# MCP23017.net
KiCad netlist of a schematic drawn in Altium Designer
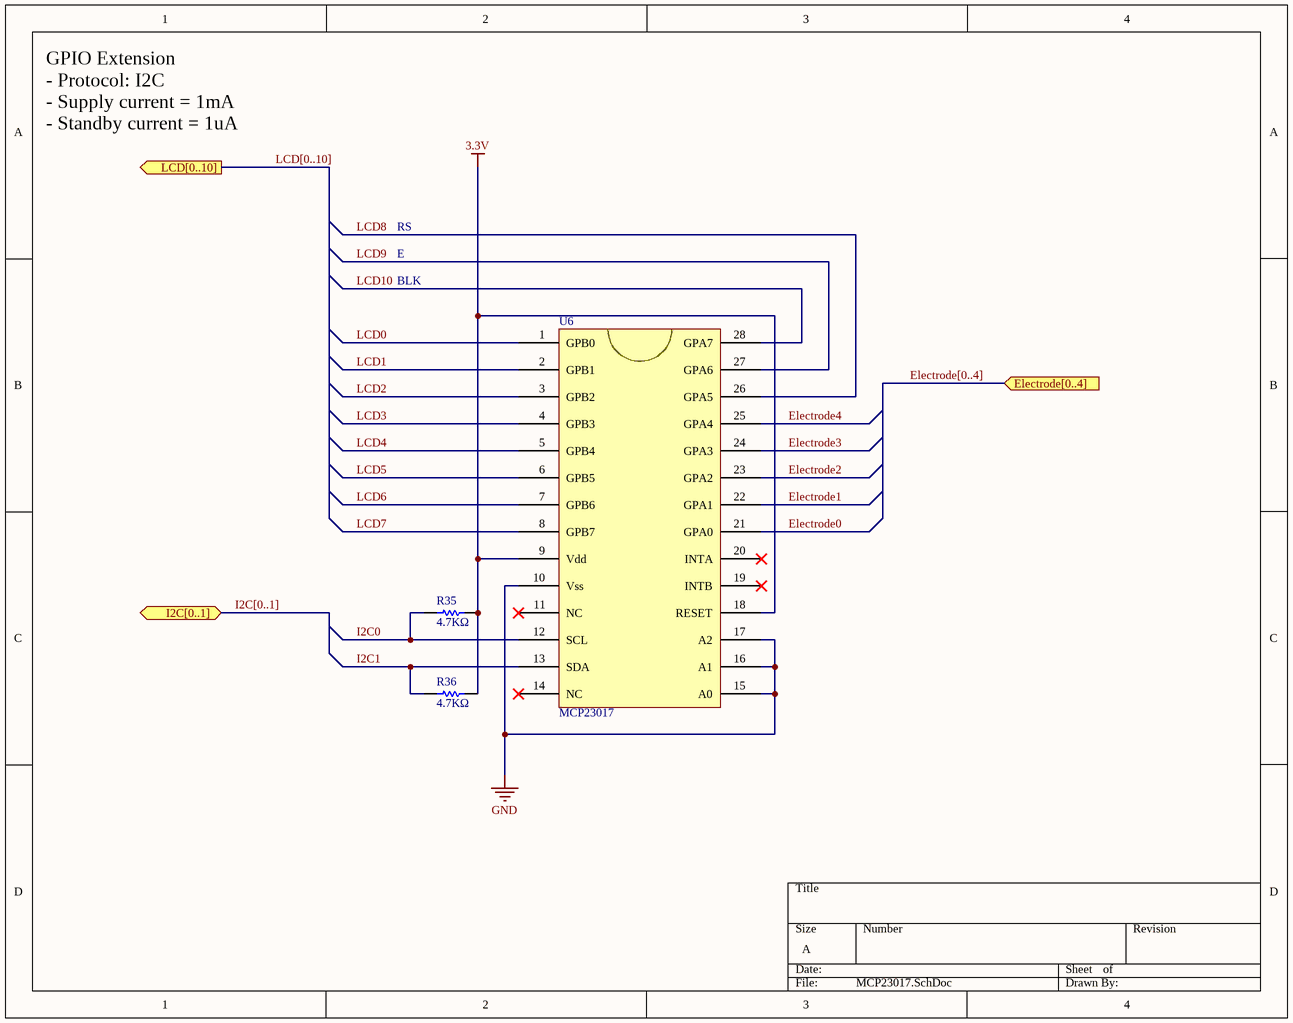
[diagram p0: MCP23017.SchDoc]

(export (version "E")
  (design (tool "Eeschema 10.0.6"))
  (components
    (comp (ref "R35")
      (value "4.7KΩ")
      (footprint "R0603")
      (description "Resistor")
      (fields (field (name "MANUFACTURER") "MULTICOMP") (field (name "PUBLISHER") "Altium Limited"))
      (libsource (lib "Miscellaneous Devices") (part "Res1"))
    )
    (comp (ref "R36")
      (value "4.7KΩ")
      (footprint "R0603")
      (description "Resistor")
      (fields (field (name "MANUFACTURER") "MULTICOMP") (field (name "PUBLISHER") "Altium Limited"))
      (libsource (lib "Miscellaneous Devices") (part "Res1"))
    )
    (comp (ref "U6")
      (value "MCP23017")
      (footprint "MCP23017")
      (description "GPIOExpander")
      (fields (field (name "MANUFACTURER") "MICROCHIP"))
      (libsource (lib "Electroplant") (part "MPC23017"))
    )
  )
  (nets
    (net (code "1") (name "/Electrode0") (class "Default")
      (node (ref "U6") (pin "21") (pinfunction "GPA0_21") (pintype "passive"))
    )
    (net (code "2") (name "/Electrode1") (class "Default")
      (node (ref "U6") (pin "22") (pinfunction "GPA1_22") (pintype "passive"))
    )
    (net (code "3") (name "/Electrode2") (class "Default")
      (node (ref "U6") (pin "23") (pinfunction "GPA2_23") (pintype "passive"))
    )
    (net (code "4") (name "/Electrode3") (class "Default")
      (node (ref "U6") (pin "24") (pinfunction "GPA3_24") (pintype "passive"))
    )
    (net (code "5") (name "/Electrode4") (class "Default")
      (node (ref "U6") (pin "25") (pinfunction "GPA4_25") (pintype "passive"))
    )
    (net (code "7") (name "/I2C0") (class "Default")
      (node (ref "R35") (pin "1") (pinfunction "1_1") (pintype "passive"))
      (node (ref "U6") (pin "12") (pinfunction "SCL_12") (pintype "passive"))
    )
    (net (code "8") (name "/I2C1") (class "Default")
      (node (ref "R36") (pin "1") (pinfunction "1_1") (pintype "passive"))
      (node (ref "U6") (pin "13") (pinfunction "SDA_13") (pintype "passive"))
    )
    (net (code "10") (name "/LCD0") (class "Default")
      (node (ref "U6") (pin "1") (pinfunction "GPB0_1") (pintype "passive"))
    )
    (net (code "11") (name "/LCD1") (class "Default")
      (node (ref "U6") (pin "2") (pinfunction "GPB1_2") (pintype "passive"))
    )
    (net (code "12") (name "/LCD2") (class "Default")
      (node (ref "U6") (pin "3") (pinfunction "GPB2_3") (pintype "passive"))
    )
    (net (code "13") (name "/LCD3") (class "Default")
      (node (ref "U6") (pin "4") (pinfunction "GPB3_4") (pintype "passive"))
    )
    (net (code "14") (name "/LCD4") (class "Default")
      (node (ref "U6") (pin "5") (pinfunction "GPB4_5") (pintype "passive"))
    )
    (net (code "15") (name "/LCD5") (class "Default")
      (node (ref "U6") (pin "6") (pinfunction "GPB5_6") (pintype "passive"))
    )
    (net (code "16") (name "/LCD6") (class "Default")
      (node (ref "U6") (pin "7") (pinfunction "GPB6_7") (pintype "passive"))
    )
    (net (code "17") (name "/LCD7") (class "Default")
      (node (ref "U6") (pin "8") (pinfunction "GPB7_8") (pintype "passive"))
    )
    (net (code "18") (name "/LCD8") (class "Default")
      (node (ref "U6") (pin "26") (pinfunction "GPA5_26") (pintype "passive"))
    )
    (net (code "19") (name "/LCD9") (class "Default")
      (node (ref "U6") (pin "27") (pinfunction "GPA6_27") (pintype "passive"))
    )
    (net (code "20") (name "/LCD10") (class "Default")
      (node (ref "U6") (pin "28") (pinfunction "GPA7_28") (pintype "passive"))
    )
    (net (code "22") (name "3.3V") (class "Default")
      (node (ref "R35") (pin "2") (pinfunction "2_2") (pintype "passive"))
      (node (ref "R36") (pin "2") (pinfunction "2_2") (pintype "passive"))
      (node (ref "U6") (pin "18") (pinfunction "RESET_18") (pintype "passive"))
      (node (ref "U6") (pin "9") (pinfunction "Vdd_9") (pintype "passive"))
    )
    (net (code "23") (name "GND") (class "Default")
      (node (ref "U6") (pin "10") (pinfunction "Vss_10") (pintype "passive"))
      (node (ref "U6") (pin "15") (pinfunction "A0_15") (pintype "passive"))
      (node (ref "U6") (pin "16") (pinfunction "A1_16") (pintype "passive"))
      (node (ref "U6") (pin "17") (pinfunction "A2_17") (pintype "passive"))
    )
    (net (code "24") (name "unconnected-(U6-INTA-Pad20)") (class "Default")
      (node (ref "U6") (pin "20") (pinfunction "INTA_20") (pintype "passive+no_connect"))
    )
    (net (code "25") (name "unconnected-(U6-INTB-Pad19)") (class "Default")
      (node (ref "U6") (pin "19") (pinfunction "INTB_19") (pintype "passive+no_connect"))
    )
    (net (code "26") (name "unconnected-(U6-NC-Pad11)") (class "Default")
      (node (ref "U6") (pin "11") (pinfunction "NC_11") (pintype "passive+no_connect"))
    )
    (net (code "27") (name "unconnected-(U6-NC-Pad14)") (class "Default")
      (node (ref "U6") (pin "14") (pinfunction "NC_14") (pintype "passive+no_connect"))
    )
  )
)
